# Tilty_Omni.net
KiCad netlist of a schematic drawn in EAGLE
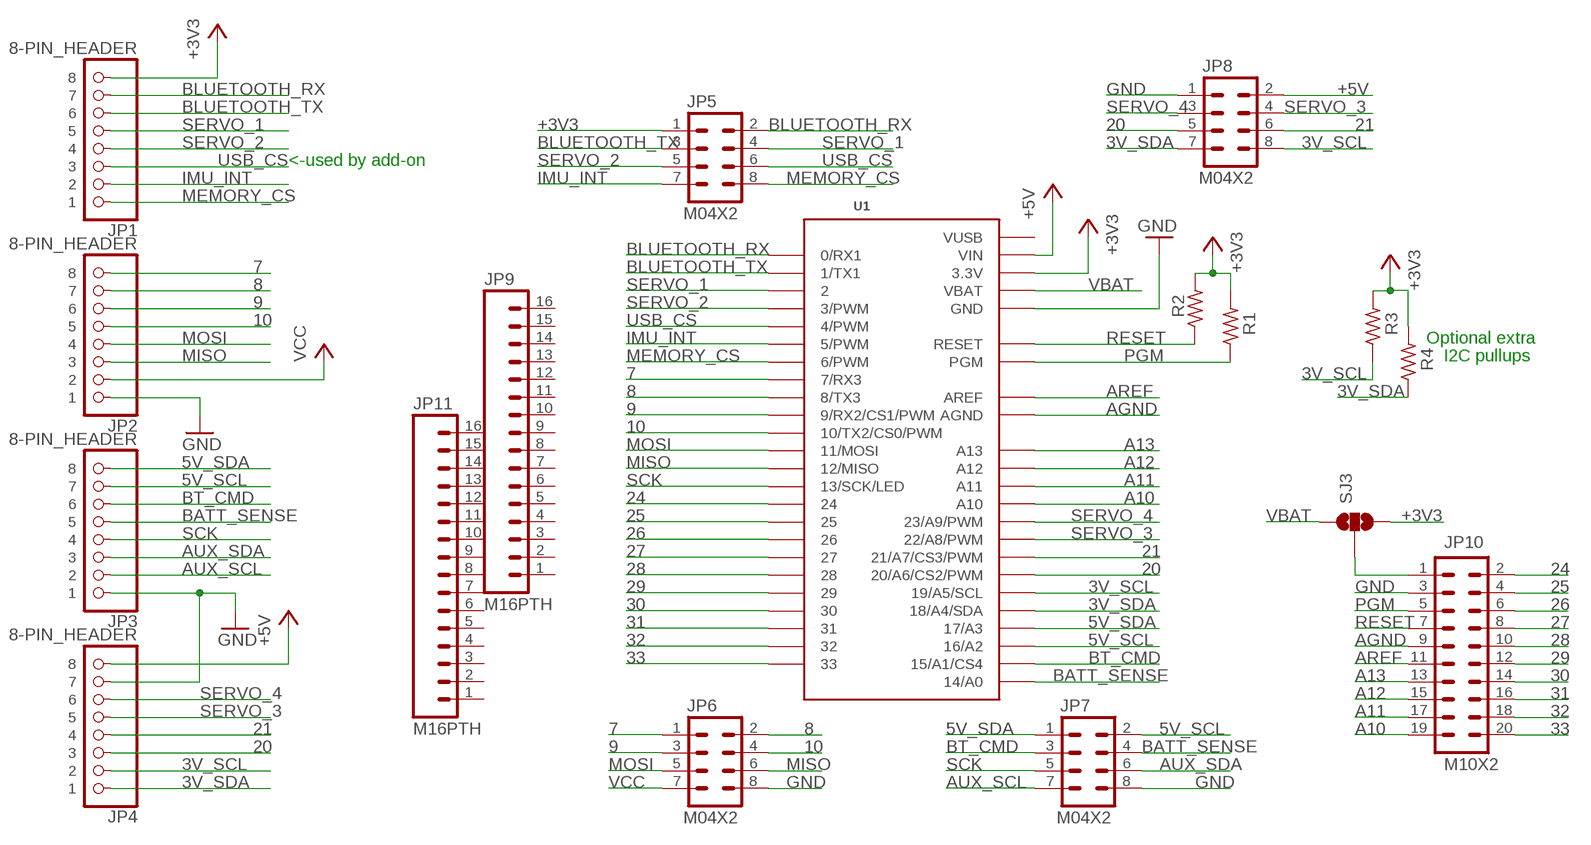
[diagram p0: schematic, sheet 1]

(export (version "E")
  (design (tool "Eeschema 10.0.6"))
  (components
    (comp (ref "JP1")
      (value "8-PIN_HEADER")
      (footprint "eagle-import:8-PIN_RECEPTACLE_LOCK_NO-SS")
      (libsource (lib "eagle-import") (part "8-PIN_HEADER"))
    )
    (comp (ref "JP2")
      (value "8-PIN_HEADER")
      (footprint "eagle-import:8-PIN_RECEPTACLE_LOCK_NO-SS")
      (libsource (lib "eagle-import") (part "8-PIN_HEADER"))
    )
    (comp (ref "JP3")
      (value "8-PIN_HEADER")
      (footprint "eagle-import:8-PIN_RECEPTACLE_LOCK_NO-SS")
      (libsource (lib "eagle-import") (part "8-PIN_HEADER"))
    )
    (comp (ref "JP4")
      (value "8-PIN_HEADER")
      (footprint "eagle-import:8-PIN_RECEPTACLE_LOCK_NO-SS")
      (libsource (lib "eagle-import") (part "8-PIN_HEADER"))
    )
    (comp (ref "JP5")
      (value "M04X2")
      (footprint "eagle-import:2X4")
      (libsource (lib "eagle-import") (part "M04X2"))
    )
    (comp (ref "JP6")
      (value "M04X2")
      (footprint "eagle-import:2X4")
      (libsource (lib "eagle-import") (part "M04X2"))
    )
    (comp (ref "JP7")
      (value "M04X2")
      (footprint "eagle-import:2X4")
      (libsource (lib "eagle-import") (part "M04X2"))
    )
    (comp (ref "JP8")
      (value "M04X2")
      (footprint "eagle-import:2X4")
      (libsource (lib "eagle-import") (part "M04X2"))
    )
    (comp (ref "JP9")
      (value "M16PTH")
      (footprint "eagle-import:1X16")
      (libsource (lib "eagle-import") (part "M16PTH"))
    )
    (comp (ref "JP10")
      (value "M10X2")
      (footprint "eagle-import:2X10")
      (libsource (lib "eagle-import") (part "M10X2"))
    )
    (comp (ref "JP11")
      (value "M16PTH")
      (footprint "eagle-import:1X16")
      (libsource (lib "eagle-import") (part "M16PTH"))
    )
    (comp (ref "R1")
      (value "10k")
      (footprint "eagle-import:R0603")
      (libsource (lib "eagle-import") (part "R-US_R0603"))
    )
    (comp (ref "R2")
      (value "10k")
      (footprint "eagle-import:R0603")
      (libsource (lib "eagle-import") (part "R-US_R0603"))
    )
    (comp (ref "R3")
      (value "10k")
      (footprint "eagle-import:R0603")
      (libsource (lib "eagle-import") (part "R-US_R0603"))
    )
    (comp (ref "R4")
      (value "10k")
      (footprint "eagle-import:R0603")
      (libsource (lib "eagle-import") (part "R-US_R0603"))
    )
    (comp (ref "SJ3")
      (value "SOLDERJUMPER_2WAYPASTE2&3")
      (footprint "eagle-import:SJ_3_PASTE2&3")
      (libsource (lib "eagle-import") (part "SOLDERJUMPER_2WAYPASTE2&3"))
    )
    (comp (ref "U1")
      (value "TEENSY_3.0_ALLPINS")
      (footprint "eagle-import:TEENSY_3.0_ALLPINS")
      (libsource (lib "eagle-import") (part "TEENSY_3.0_ALLPINS"))
    )
  )
  (nets
    (net (code "1") (name "+3V3") (class "Default")
      (node (ref "JP1") (pin "P$8") (pinfunction "8_P$8") (pintype "passive"))
      (node (ref "JP5") (pin "1") (pinfunction "1_1") (pintype "passive"))
      (node (ref "R1") (pin "2") (pinfunction "2_2") (pintype "passive"))
      (node (ref "R2") (pin "2") (pinfunction "2_2") (pintype "passive"))
      (node (ref "R3") (pin "2") (pinfunction "2_2") (pintype "passive"))
      (node (ref "R4") (pin "2") (pinfunction "2_2") (pintype "passive"))
      (node (ref "SJ3") (pin "3") (pinfunction "3_3") (pintype "passive"))
      (node (ref "U1") (pin "3.3V") (pinfunction "3.3V_3.3V") (pintype "power_in"))
      (node (ref "U1") (pin "3.3V1") (pinfunction "3.3V_3.3V1") (pintype "power_in"))
      (node (ref "U1") (pin "3.3V2") (pinfunction "3.3V_3.3V2") (pintype "power_in"))
    )
    (net (code "2") (name "+5V") (class "Default")
      (node (ref "JP4") (pin "P$8") (pinfunction "8_P$8") (pintype "passive"))
      (node (ref "JP8") (pin "2") (pinfunction "2_2") (pintype "passive"))
      (node (ref "U1") (pin "VIN") (pinfunction "VIN_VIN") (pintype "power_in"))
    )
    (net (code "3") (name "/3V_SCL") (class "Default")
      (node (ref "JP4") (pin "P$2") (pinfunction "2_P$2") (pintype "passive"))
      (node (ref "JP8") (pin "8") (pinfunction "8_8") (pintype "passive"))
      (node (ref "R3") (pin "1") (pinfunction "1_1") (pintype "passive"))
      (node (ref "U1") (pin "19/A5") (pinfunction "19/A5/SCL_19/A5") (pintype "bidirectional"))
    )
    (net (code "4") (name "/3V_SDA") (class "Default")
      (node (ref "JP4") (pin "P$1") (pinfunction "1_P$1") (pintype "passive"))
      (node (ref "JP8") (pin "7") (pinfunction "7_7") (pintype "passive"))
      (node (ref "R4") (pin "1") (pinfunction "1_1") (pintype "passive"))
      (node (ref "U1") (pin "18/A4") (pinfunction "18/A4/SDA_18/A4") (pintype "bidirectional"))
    )
    (net (code "5") (name "/5V_SCL") (class "Default")
      (node (ref "JP3") (pin "P$7") (pinfunction "7_P$7") (pintype "passive"))
      (node (ref "JP7") (pin "2") (pinfunction "2_2") (pintype "passive"))
      (node (ref "U1") (pin "16/A2") (pinfunction "16/A2_16/A2") (pintype "bidirectional"))
    )
    (net (code "6") (name "/5V_SDA") (class "Default")
      (node (ref "JP3") (pin "P$8") (pinfunction "8_P$8") (pintype "passive"))
      (node (ref "JP7") (pin "1") (pinfunction "1_1") (pintype "passive"))
      (node (ref "U1") (pin "17/A3") (pinfunction "17/A3_17/A3") (pintype "bidirectional"))
    )
    (net (code "7") (name "/7") (class "Default")
      (node (ref "JP2") (pin "P$8") (pinfunction "8_P$8") (pintype "passive"))
      (node (ref "JP6") (pin "1") (pinfunction "1_1") (pintype "passive"))
      (node (ref "U1") (pin "7") (pinfunction "7/RX3_7") (pintype "bidirectional"))
    )
    (net (code "8") (name "/8") (class "Default")
      (node (ref "JP2") (pin "P$7") (pinfunction "7_P$7") (pintype "passive"))
      (node (ref "JP6") (pin "2") (pinfunction "2_2") (pintype "passive"))
      (node (ref "U1") (pin "8") (pinfunction "8/TX3_8") (pintype "bidirectional"))
    )
    (net (code "9") (name "/9") (class "Default")
      (node (ref "JP2") (pin "P$6") (pinfunction "6_P$6") (pintype "passive"))
      (node (ref "JP6") (pin "3") (pinfunction "3_3") (pintype "passive"))
      (node (ref "U1") (pin "9") (pinfunction "9/RX2/CS1/PWM_9") (pintype "bidirectional"))
    )
    (net (code "10") (name "/10") (class "Default")
      (node (ref "JP2") (pin "P$5") (pinfunction "5_P$5") (pintype "passive"))
      (node (ref "JP6") (pin "4") (pinfunction "4_4") (pintype "passive"))
      (node (ref "U1") (pin "10") (pinfunction "10/TX2/CS0/PWM_10") (pintype "bidirectional"))
    )
    (net (code "11") (name "/20") (class "Default")
      (node (ref "JP4") (pin "P$3") (pinfunction "3_P$3") (pintype "passive"))
      (node (ref "JP8") (pin "5") (pinfunction "5_5") (pintype "passive"))
      (node (ref "U1") (pin "20/A6") (pinfunction "20/A6/CS2/PWM_20/A6") (pintype "bidirectional"))
    )
    (net (code "12") (name "/21") (class "Default")
      (node (ref "JP4") (pin "P$4") (pinfunction "4_P$4") (pintype "passive"))
      (node (ref "JP8") (pin "6") (pinfunction "6_6") (pintype "passive"))
      (node (ref "U1") (pin "21/A7") (pinfunction "21/A7/CS3/PWM_21/A7") (pintype "bidirectional"))
    )
    (net (code "13") (name "/24") (class "Default")
      (node (ref "JP10") (pin "2") (pinfunction "2_2") (pintype "passive"))
      (node (ref "U1") (pin "24") (pinfunction "24_24") (pintype "bidirectional"))
    )
    (net (code "14") (name "/25") (class "Default")
      (node (ref "JP10") (pin "4") (pinfunction "4_4") (pintype "passive"))
      (node (ref "U1") (pin "25") (pinfunction "25_25") (pintype "bidirectional"))
    )
    (net (code "15") (name "/26") (class "Default")
      (node (ref "JP10") (pin "6") (pinfunction "6_6") (pintype "passive"))
      (node (ref "U1") (pin "26") (pinfunction "26_26") (pintype "bidirectional"))
    )
    (net (code "16") (name "/27") (class "Default")
      (node (ref "JP10") (pin "8") (pinfunction "8_8") (pintype "passive"))
      (node (ref "U1") (pin "27") (pinfunction "27_27") (pintype "bidirectional"))
    )
    (net (code "17") (name "/28") (class "Default")
      (node (ref "JP10") (pin "10") (pinfunction "10_10") (pintype "passive"))
      (node (ref "U1") (pin "28") (pinfunction "28_28") (pintype "bidirectional"))
    )
    (net (code "18") (name "/29") (class "Default")
      (node (ref "JP10") (pin "12") (pinfunction "12_12") (pintype "passive"))
      (node (ref "U1") (pin "29") (pinfunction "29_29") (pintype "bidirectional"))
    )
    (net (code "19") (name "/30") (class "Default")
      (node (ref "JP10") (pin "14") (pinfunction "14_14") (pintype "passive"))
      (node (ref "U1") (pin "30") (pinfunction "30_30") (pintype "bidirectional"))
    )
    (net (code "20") (name "/31") (class "Default")
      (node (ref "JP10") (pin "16") (pinfunction "16_16") (pintype "passive"))
      (node (ref "U1") (pin "31") (pinfunction "31_31") (pintype "bidirectional"))
    )
    (net (code "21") (name "/32") (class "Default")
      (node (ref "JP10") (pin "18") (pinfunction "18_18") (pintype "passive"))
      (node (ref "U1") (pin "32") (pinfunction "32_32") (pintype "bidirectional"))
    )
    (net (code "22") (name "/33") (class "Default")
      (node (ref "JP10") (pin "20") (pinfunction "20_20") (pintype "passive"))
      (node (ref "U1") (pin "33") (pinfunction "33_33") (pintype "bidirectional"))
    )
    (net (code "23") (name "/A10") (class "Default")
      (node (ref "JP10") (pin "19") (pinfunction "19_19") (pintype "passive"))
      (node (ref "U1") (pin "A10") (pinfunction "A10_A10") (pintype "bidirectional"))
    )
    (net (code "24") (name "/A11") (class "Default")
      (node (ref "JP10") (pin "17") (pinfunction "17_17") (pintype "passive"))
      (node (ref "U1") (pin "A11") (pinfunction "A11_A11") (pintype "bidirectional"))
    )
    (net (code "25") (name "/A12") (class "Default")
      (node (ref "JP10") (pin "15") (pinfunction "15_15") (pintype "passive"))
      (node (ref "U1") (pin "A12") (pinfunction "A12_A12") (pintype "bidirectional"))
    )
    (net (code "26") (name "/A13") (class "Default")
      (node (ref "JP10") (pin "13") (pinfunction "13_13") (pintype "passive"))
      (node (ref "U1") (pin "A13") (pinfunction "A13_A13") (pintype "bidirectional"))
    )
    (net (code "27") (name "/AGND") (class "Default")
      (node (ref "JP10") (pin "9") (pinfunction "9_9") (pintype "passive"))
      (node (ref "U1") (pin "AGND") (pinfunction "AGND_AGND") (pintype "power_in"))
    )
    (net (code "28") (name "/AREF") (class "Default")
      (node (ref "JP10") (pin "11") (pinfunction "11_11") (pintype "passive"))
      (node (ref "U1") (pin "AREF") (pinfunction "AREF_AREF") (pintype "power_in"))
    )
    (net (code "29") (name "/AUX_SCL") (class "Default")
      (node (ref "JP3") (pin "P$2") (pinfunction "2_P$2") (pintype "passive"))
      (node (ref "JP7") (pin "7") (pinfunction "7_7") (pintype "passive"))
    )
    (net (code "30") (name "/AUX_SDA") (class "Default")
      (node (ref "JP3") (pin "P$3") (pinfunction "3_P$3") (pintype "passive"))
      (node (ref "JP7") (pin "6") (pinfunction "6_6") (pintype "passive"))
    )
    (net (code "31") (name "/BATT_SENSE") (class "Default")
      (node (ref "JP3") (pin "P$5") (pinfunction "5_P$5") (pintype "passive"))
      (node (ref "JP7") (pin "4") (pinfunction "4_4") (pintype "passive"))
      (node (ref "U1") (pin "14/A0") (pinfunction "14/A0_14/A0") (pintype "bidirectional"))
    )
    (net (code "32") (name "/BLUETOOTH_RX") (class "Default")
      (node (ref "JP1") (pin "P$7") (pinfunction "7_P$7") (pintype "passive"))
      (node (ref "JP5") (pin "2") (pinfunction "2_2") (pintype "passive"))
      (node (ref "U1") (pin "0") (pinfunction "0/RX1_0") (pintype "bidirectional"))
    )
    (net (code "33") (name "/BLUETOOTH_TX") (class "Default")
      (node (ref "JP1") (pin "P$6") (pinfunction "6_P$6") (pintype "passive"))
      (node (ref "JP5") (pin "3") (pinfunction "3_3") (pintype "passive"))
      (node (ref "U1") (pin "1") (pinfunction "1/TX1_1") (pintype "bidirectional"))
    )
    (net (code "34") (name "/BT_CMD") (class "Default")
      (node (ref "JP3") (pin "P$6") (pinfunction "6_P$6") (pintype "passive"))
      (node (ref "JP7") (pin "3") (pinfunction "3_3") (pintype "passive"))
      (node (ref "U1") (pin "15/A1") (pinfunction "15/A1/CS4_15/A1") (pintype "bidirectional"))
    )
    (net (code "35") (name "/IMU_INT") (class "Default")
      (node (ref "JP1") (pin "P$2") (pinfunction "2_P$2") (pintype "passive"))
      (node (ref "JP5") (pin "7") (pinfunction "7_7") (pintype "passive"))
      (node (ref "U1") (pin "5") (pinfunction "5/PWM_5") (pintype "bidirectional"))
    )
    (net (code "36") (name "/MEMORY_CS") (class "Default")
      (node (ref "JP1") (pin "P$1") (pinfunction "1_P$1") (pintype "passive"))
      (node (ref "JP5") (pin "8") (pinfunction "8_8") (pintype "passive"))
      (node (ref "U1") (pin "6") (pinfunction "6/PWM_6") (pintype "bidirectional"))
    )
    (net (code "37") (name "/MISO") (class "Default")
      (node (ref "JP2") (pin "P$3") (pinfunction "3_P$3") (pintype "passive"))
      (node (ref "JP6") (pin "6") (pinfunction "6_6") (pintype "passive"))
      (node (ref "U1") (pin "12") (pinfunction "12/MISO_12") (pintype "bidirectional"))
    )
    (net (code "38") (name "/MOSI") (class "Default")
      (node (ref "JP2") (pin "P$4") (pinfunction "4_P$4") (pintype "passive"))
      (node (ref "JP6") (pin "5") (pinfunction "5_5") (pintype "passive"))
      (node (ref "U1") (pin "11") (pinfunction "11/MOSI_11") (pintype "bidirectional"))
    )
    (net (code "39") (name "/PGM") (class "Default")
      (node (ref "JP10") (pin "5") (pinfunction "5_5") (pintype "passive"))
      (node (ref "R1") (pin "1") (pinfunction "1_1") (pintype "passive"))
      (node (ref "U1") (pin "PGM") (pinfunction "PGM_PGM") (pintype "bidirectional"))
    )
    (net (code "40") (name "/RESET") (class "Default")
      (node (ref "JP10") (pin "7") (pinfunction "7_7") (pintype "passive"))
      (node (ref "R2") (pin "1") (pinfunction "1_1") (pintype "passive"))
      (node (ref "U1") (pin "RESET") (pinfunction "RESET_RESET") (pintype "bidirectional"))
    )
    (net (code "41") (name "/SCK") (class "Default")
      (node (ref "JP3") (pin "P$4") (pinfunction "4_P$4") (pintype "passive"))
      (node (ref "JP7") (pin "5") (pinfunction "5_5") (pintype "passive"))
      (node (ref "U1") (pin "13") (pinfunction "13/SCK/LED_13") (pintype "bidirectional"))
    )
    (net (code "42") (name "/SERVO_1") (class "Default")
      (node (ref "JP1") (pin "P$5") (pinfunction "5_P$5") (pintype "passive"))
      (node (ref "JP5") (pin "4") (pinfunction "4_4") (pintype "passive"))
      (node (ref "U1") (pin "2") (pinfunction "2_2") (pintype "bidirectional"))
    )
    (net (code "43") (name "/SERVO_2") (class "Default")
      (node (ref "JP1") (pin "P$4") (pinfunction "4_P$4") (pintype "passive"))
      (node (ref "JP5") (pin "5") (pinfunction "5_5") (pintype "passive"))
      (node (ref "U1") (pin "3") (pinfunction "3/PWM_3") (pintype "bidirectional"))
    )
    (net (code "44") (name "/SERVO_3") (class "Default")
      (node (ref "JP4") (pin "P$5") (pinfunction "5_P$5") (pintype "passive"))
      (node (ref "JP8") (pin "4") (pinfunction "4_4") (pintype "passive"))
      (node (ref "U1") (pin "22/A8") (pinfunction "22/A8/PWM_22/A8") (pintype "bidirectional"))
    )
    (net (code "45") (name "/SERVO_4") (class "Default")
      (node (ref "JP4") (pin "P$6") (pinfunction "6_P$6") (pintype "passive"))
      (node (ref "JP8") (pin "3") (pinfunction "3_3") (pintype "passive"))
      (node (ref "U1") (pin "23/A9") (pinfunction "23/A9/PWM_23/A9") (pintype "bidirectional"))
    )
    (net (code "46") (name "/USB_CS") (class "Default")
      (node (ref "JP1") (pin "P$3") (pinfunction "3_P$3") (pintype "passive"))
      (node (ref "JP5") (pin "6") (pinfunction "6_6") (pintype "passive"))
      (node (ref "U1") (pin "4") (pinfunction "4/PWM_4") (pintype "bidirectional"))
    )
    (net (code "47") (name "/VBAT") (class "Default")
      (node (ref "SJ3") (pin "1") (pinfunction "1_1") (pintype "passive"))
      (node (ref "U1") (pin "VBAT") (pinfunction "VBAT_VBAT") (pintype "power_in"))
    )
    (net (code "48") (name "/VUSB") (class "Default")
      (node (ref "U1") (pin "VUSB") (pinfunction "VUSB_VUSB") (pintype "power_in"))
    )
    (net (code "49") (name "GND") (class "Default")
      (node (ref "JP10") (pin "3") (pinfunction "3_3") (pintype "passive"))
      (node (ref "JP2") (pin "P$1") (pinfunction "1_P$1") (pintype "passive"))
      (node (ref "JP3") (pin "P$1") (pinfunction "1_P$1") (pintype "passive"))
      (node (ref "JP4") (pin "P$7") (pinfunction "7_P$7") (pintype "passive"))
      (node (ref "JP6") (pin "8") (pinfunction "8_8") (pintype "passive"))
      (node (ref "JP7") (pin "8") (pinfunction "8_8") (pintype "passive"))
      (node (ref "JP8") (pin "1") (pinfunction "1_1") (pintype "passive"))
      (node (ref "U1") (pin "GND") (pinfunction "GND_GND") (pintype "power_in"))
      (node (ref "U1") (pin "GND1") (pinfunction "GND_GND1") (pintype "power_in"))
      (node (ref "U1") (pin "GND2") (pinfunction "GND_GND2") (pintype "power_in"))
    )
    (net (code "50") (name "Net-(JP10-Pad1)") (class "Default")
      (node (ref "JP10") (pin "1") (pinfunction "1_1") (pintype "passive"))
      (node (ref "SJ3") (pin "2") (pinfunction "2_2") (pintype "passive"))
    )
    (net (code "51") (name "VCC") (class "Default")
      (node (ref "JP2") (pin "P$2") (pinfunction "2_P$2") (pintype "passive"))
      (node (ref "JP6") (pin "7") (pinfunction "7_7") (pintype "passive"))
    )
    (net (code "52") (name "unconnected-(JP9-Pad1)") (class "Default")
      (node (ref "JP9") (pin "1") (pinfunction "1_1") (pintype "passive"))
    )
    (net (code "53") (name "unconnected-(JP9-Pad2)") (class "Default")
      (node (ref "JP9") (pin "2") (pinfunction "2_2") (pintype "passive"))
    )
    (net (code "54") (name "unconnected-(JP9-Pad3)") (class "Default")
      (node (ref "JP9") (pin "3") (pinfunction "3_3") (pintype "passive"))
    )
    (net (code "55") (name "unconnected-(JP9-Pad4)") (class "Default")
      (node (ref "JP9") (pin "4") (pinfunction "4_4") (pintype "passive"))
    )
    (net (code "56") (name "unconnected-(JP9-Pad5)") (class "Default")
      (node (ref "JP9") (pin "5") (pinfunction "5_5") (pintype "passive"))
    )
    (net (code "57") (name "unconnected-(JP9-Pad6)") (class "Default")
      (node (ref "JP9") (pin "6") (pinfunction "6_6") (pintype "passive"))
    )
    (net (code "58") (name "unconnected-(JP9-Pad7)") (class "Default")
      (node (ref "JP9") (pin "7") (pinfunction "7_7") (pintype "passive"))
    )
    (net (code "59") (name "unconnected-(JP9-Pad8)") (class "Default")
      (node (ref "JP9") (pin "8") (pinfunction "8_8") (pintype "passive"))
    )
    (net (code "60") (name "unconnected-(JP9-Pad9)") (class "Default")
      (node (ref "JP9") (pin "9") (pinfunction "9_9") (pintype "passive"))
    )
    (net (code "61") (name "unconnected-(JP9-Pad10)") (class "Default")
      (node (ref "JP9") (pin "10") (pinfunction "10_10") (pintype "passive"))
    )
    (net (code "62") (name "unconnected-(JP9-Pad11)") (class "Default")
      (node (ref "JP9") (pin "11") (pinfunction "11_11") (pintype "passive"))
    )
    (net (code "63") (name "unconnected-(JP9-Pad12)") (class "Default")
      (node (ref "JP9") (pin "12") (pinfunction "12_12") (pintype "passive"))
    )
    (net (code "64") (name "unconnected-(JP9-Pad13)") (class "Default")
      (node (ref "JP9") (pin "13") (pinfunction "13_13") (pintype "passive"))
    )
    (net (code "65") (name "unconnected-(JP9-Pad14)") (class "Default")
      (node (ref "JP9") (pin "14") (pinfunction "14_14") (pintype "passive"))
    )
    (net (code "66") (name "unconnected-(JP9-Pad15)") (class "Default")
      (node (ref "JP9") (pin "15") (pinfunction "15_15") (pintype "passive"))
    )
    (net (code "67") (name "unconnected-(JP9-Pad16)") (class "Default")
      (node (ref "JP9") (pin "16") (pinfunction "16_16") (pintype "passive"))
    )
    (net (code "68") (name "unconnected-(JP11-Pad1)") (class "Default")
      (node (ref "JP11") (pin "1") (pinfunction "1_1") (pintype "passive"))
    )
    (net (code "69") (name "unconnected-(JP11-Pad2)") (class "Default")
      (node (ref "JP11") (pin "2") (pinfunction "2_2") (pintype "passive"))
    )
    (net (code "70") (name "unconnected-(JP11-Pad3)") (class "Default")
      (node (ref "JP11") (pin "3") (pinfunction "3_3") (pintype "passive"))
    )
    (net (code "71") (name "unconnected-(JP11-Pad4)") (class "Default")
      (node (ref "JP11") (pin "4") (pinfunction "4_4") (pintype "passive"))
    )
    (net (code "72") (name "unconnected-(JP11-Pad5)") (class "Default")
      (node (ref "JP11") (pin "5") (pinfunction "5_5") (pintype "passive"))
    )
    (net (code "73") (name "unconnected-(JP11-Pad6)") (class "Default")
      (node (ref "JP11") (pin "6") (pinfunction "6_6") (pintype "passive"))
    )
    (net (code "74") (name "unconnected-(JP11-Pad7)") (class "Default")
      (node (ref "JP11") (pin "7") (pinfunction "7_7") (pintype "passive"))
    )
    (net (code "75") (name "unconnected-(JP11-Pad8)") (class "Default")
      (node (ref "JP11") (pin "8") (pinfunction "8_8") (pintype "passive"))
    )
    (net (code "76") (name "unconnected-(JP11-Pad9)") (class "Default")
      (node (ref "JP11") (pin "9") (pinfunction "9_9") (pintype "passive"))
    )
    (net (code "77") (name "unconnected-(JP11-Pad10)") (class "Default")
      (node (ref "JP11") (pin "10") (pinfunction "10_10") (pintype "passive"))
    )
    (net (code "78") (name "unconnected-(JP11-Pad11)") (class "Default")
      (node (ref "JP11") (pin "11") (pinfunction "11_11") (pintype "passive"))
    )
    (net (code "79") (name "unconnected-(JP11-Pad12)") (class "Default")
      (node (ref "JP11") (pin "12") (pinfunction "12_12") (pintype "passive"))
    )
    (net (code "80") (name "unconnected-(JP11-Pad13)") (class "Default")
      (node (ref "JP11") (pin "13") (pinfunction "13_13") (pintype "passive"))
    )
    (net (code "81") (name "unconnected-(JP11-Pad14)") (class "Default")
      (node (ref "JP11") (pin "14") (pinfunction "14_14") (pintype "passive"))
    )
    (net (code "82") (name "unconnected-(JP11-Pad15)") (class "Default")
      (node (ref "JP11") (pin "15") (pinfunction "15_15") (pintype "passive"))
    )
    (net (code "83") (name "unconnected-(JP11-Pad16)") (class "Default")
      (node (ref "JP11") (pin "16") (pinfunction "16_16") (pintype "passive"))
    )
  )
)
